# ESP.net
KiCad netlist of a schematic drawn in EAGLE
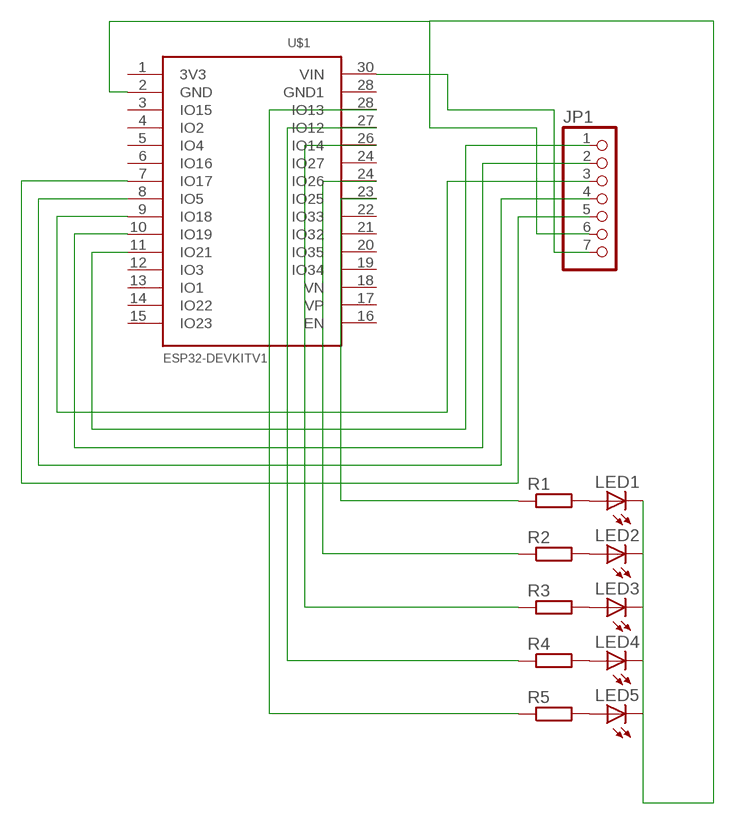
[diagram p0: schematic, sheet 1]

(export (version "E")
  (design (tool "Eeschema 10.0.6"))
  (components
    (comp (ref "JP1")
      (value "PINHD-1X7")
      (footprint "eagle-import:1X07")
      (libsource (lib "eagle-import") (part "PINHD-1X7"))
    )
    (comp (ref "LED1")
      (value "LED5MM")
      (footprint "eagle-import:LED5MM")
      (libsource (lib "eagle-import") (part "LED5MM"))
    )
    (comp (ref "LED2")
      (value "LED5MM")
      (footprint "eagle-import:LED5MM")
      (libsource (lib "eagle-import") (part "LED5MM"))
    )
    (comp (ref "LED3")
      (value "LED5MM")
      (footprint "eagle-import:LED5MM")
      (libsource (lib "eagle-import") (part "LED5MM"))
    )
    (comp (ref "LED4")
      (value "LED5MM")
      (footprint "eagle-import:LED5MM")
      (libsource (lib "eagle-import") (part "LED5MM"))
    )
    (comp (ref "LED5")
      (value "LED5MM")
      (footprint "eagle-import:LED5MM")
      (libsource (lib "eagle-import") (part "LED5MM"))
    )
    (comp (ref "R1")
      (value "R-EU_0207/7")
      (footprint "eagle-import:0207_7")
      (libsource (lib "eagle-import") (part "R-EU_0207/7"))
    )
    (comp (ref "R2")
      (value "R-EU_0207/7")
      (footprint "eagle-import:0207_7")
      (libsource (lib "eagle-import") (part "R-EU_0207/7"))
    )
    (comp (ref "R3")
      (value "R-EU_0207/7")
      (footprint "eagle-import:0207_7")
      (libsource (lib "eagle-import") (part "R-EU_0207/7"))
    )
    (comp (ref "R4")
      (value "R-EU_0207/7")
      (footprint "eagle-import:0207_7")
      (libsource (lib "eagle-import") (part "R-EU_0207/7"))
    )
    (comp (ref "R5")
      (value "R-EU_0207/7")
      (footprint "eagle-import:0207_7")
      (libsource (lib "eagle-import") (part "R-EU_0207/7"))
    )
    (comp (ref "U$1")
      (value "ESP32DEVKITV1")
      (footprint "eagle-import:ESP32-DEVKITV1")
      (libsource (lib "eagle-import") (part "ESP32DEVKITV1"))
    )
  )
  (nets
    (net (code "1") (name "Net-(LED1-C)") (class "Default")
      (node (ref "JP1") (pin "6") (pinfunction "6_6") (pintype "passive"))
      (node (ref "LED1") (pin "K") (pinfunction "C_K") (pintype "passive"))
      (node (ref "LED2") (pin "K") (pinfunction "C_K") (pintype "passive"))
      (node (ref "LED3") (pin "K") (pinfunction "C_K") (pintype "passive"))
      (node (ref "LED4") (pin "K") (pinfunction "C_K") (pintype "passive"))
      (node (ref "LED5") (pin "K") (pinfunction "C_K") (pintype "passive"))
      (node (ref "U$1") (pin "2") (pinfunction "GND_2") (pintype "bidirectional"))
    )
    (net (code "2") (name "Net-(LED1-PadA)") (class "Default")
      (node (ref "LED1") (pin "A") (pinfunction "A_A") (pintype "passive"))
      (node (ref "R1") (pin "2") (pinfunction "2_2") (pintype "passive"))
    )
    (net (code "3") (name "Net-(LED2-PadA)") (class "Default")
      (node (ref "LED2") (pin "A") (pinfunction "A_A") (pintype "passive"))
      (node (ref "R2") (pin "2") (pinfunction "2_2") (pintype "passive"))
    )
    (net (code "4") (name "Net-(LED3-PadA)") (class "Default")
      (node (ref "LED3") (pin "A") (pinfunction "A_A") (pintype "passive"))
      (node (ref "R3") (pin "2") (pinfunction "2_2") (pintype "passive"))
    )
    (net (code "5") (name "Net-(LED4-PadA)") (class "Default")
      (node (ref "LED4") (pin "A") (pinfunction "A_A") (pintype "passive"))
      (node (ref "R4") (pin "2") (pinfunction "2_2") (pintype "passive"))
    )
    (net (code "6") (name "Net-(LED5-PadA)") (class "Default")
      (node (ref "LED5") (pin "A") (pinfunction "A_A") (pintype "passive"))
      (node (ref "R5") (pin "2") (pinfunction "2_2") (pintype "passive"))
    )
    (net (code "7") (name "Net-(U$1-IO5)") (class "Default")
      (node (ref "JP1") (pin "4") (pinfunction "4_4") (pintype "passive"))
      (node (ref "U$1") (pin "8") (pinfunction "IO5_8") (pintype "bidirectional"))
    )
    (net (code "8") (name "Net-(U$1-IO12)") (class "Default")
      (node (ref "R4") (pin "1") (pinfunction "1_1") (pintype "passive"))
      (node (ref "U$1") (pin "27") (pinfunction "IO12_27") (pintype "bidirectional"))
    )
    (net (code "9") (name "Net-(U$1-IO13)") (class "Default")
      (node (ref "R5") (pin "1") (pinfunction "1_1") (pintype "passive"))
      (node (ref "U$1") (pin "28") (pinfunction "IO13_28") (pintype "bidirectional"))
    )
    (net (code "10") (name "Net-(U$1-IO14)") (class "Default")
      (node (ref "R3") (pin "1") (pinfunction "1_1") (pintype "passive"))
      (node (ref "U$1") (pin "26") (pinfunction "IO14_26") (pintype "bidirectional"))
    )
    (net (code "11") (name "Net-(U$1-IO17)") (class "Default")
      (node (ref "JP1") (pin "5") (pinfunction "5_5") (pintype "passive"))
      (node (ref "U$1") (pin "7") (pinfunction "IO17_7") (pintype "bidirectional"))
    )
    (net (code "12") (name "Net-(U$1-IO18)") (class "Default")
      (node (ref "JP1") (pin "3") (pinfunction "3_3") (pintype "passive"))
      (node (ref "U$1") (pin "9") (pinfunction "IO18_9") (pintype "bidirectional"))
    )
    (net (code "13") (name "Net-(U$1-IO19)") (class "Default")
      (node (ref "JP1") (pin "2") (pinfunction "2_2") (pintype "passive"))
      (node (ref "U$1") (pin "10") (pinfunction "IO19_10") (pintype "bidirectional"))
    )
    (net (code "14") (name "Net-(U$1-IO21)") (class "Default")
      (node (ref "JP1") (pin "1") (pinfunction "1_1") (pintype "passive"))
      (node (ref "U$1") (pin "11") (pinfunction "IO21_11") (pintype "bidirectional"))
    )
    (net (code "15") (name "Net-(U$1-IO25)") (class "Default")
      (node (ref "R1") (pin "1") (pinfunction "1_1") (pintype "passive"))
      (node (ref "U$1") (pin "23") (pinfunction "IO25_23") (pintype "bidirectional"))
    )
    (net (code "16") (name "Net-(U$1-IO26)") (class "Default")
      (node (ref "R2") (pin "1") (pinfunction "1_1") (pintype "passive"))
      (node (ref "U$1") (pin "24") (pinfunction "IO26_24") (pintype "bidirectional"))
    )
    (net (code "17") (name "Net-(U$1-VIN)") (class "Default")
      (node (ref "JP1") (pin "7") (pinfunction "7_7") (pintype "passive"))
      (node (ref "U$1") (pin "30") (pinfunction "VIN_30") (pintype "bidirectional"))
    )
    (net (code "18") (name "unconnected-(U$1-3V3-Pad1)") (class "Default")
      (node (ref "U$1") (pin "1") (pinfunction "3V3_1") (pintype "bidirectional"))
    )
    (net (code "19") (name "unconnected-(U$1-EN-Pad16)") (class "Default")
      (node (ref "U$1") (pin "16") (pinfunction "EN_16") (pintype "bidirectional"))
    )
    (net (code "20") (name "unconnected-(U$1-GND1-Pad28)") (class "Default")
      (node (ref "U$1") (pin "28") (pinfunction "GND1_28") (pintype "bidirectional"))
    )
    (net (code "21") (name "unconnected-(U$1-IO1-Pad13)") (class "Default")
      (node (ref "U$1") (pin "13") (pinfunction "IO1_13") (pintype "bidirectional"))
    )
    (net (code "22") (name "unconnected-(U$1-IO2-Pad4)") (class "Default")
      (node (ref "U$1") (pin "4") (pinfunction "IO2_4") (pintype "bidirectional"))
    )
    (net (code "23") (name "unconnected-(U$1-IO3-Pad12)") (class "Default")
      (node (ref "U$1") (pin "12") (pinfunction "IO3_12") (pintype "bidirectional"))
    )
    (net (code "24") (name "unconnected-(U$1-IO4-Pad5)") (class "Default")
      (node (ref "U$1") (pin "5") (pinfunction "IO4_5") (pintype "bidirectional"))
    )
    (net (code "25") (name "unconnected-(U$1-IO15-Pad3)") (class "Default")
      (node (ref "U$1") (pin "3") (pinfunction "IO15_3") (pintype "bidirectional"))
    )
    (net (code "26") (name "unconnected-(U$1-IO16-Pad6)") (class "Default")
      (node (ref "U$1") (pin "6") (pinfunction "IO16_6") (pintype "bidirectional"))
    )
    (net (code "27") (name "unconnected-(U$1-IO22-Pad14)") (class "Default")
      (node (ref "U$1") (pin "14") (pinfunction "IO22_14") (pintype "bidirectional"))
    )
    (net (code "28") (name "unconnected-(U$1-IO23-Pad15)") (class "Default")
      (node (ref "U$1") (pin "15") (pinfunction "IO23_15") (pintype "bidirectional"))
    )
    (net (code "29") (name "unconnected-(U$1-IO27-Pad24)") (class "Default")
      (node (ref "U$1") (pin "24") (pinfunction "IO27_24") (pintype "bidirectional"))
    )
    (net (code "30") (name "unconnected-(U$1-IO32-Pad21)") (class "Default")
      (node (ref "U$1") (pin "21") (pinfunction "IO32_21") (pintype "bidirectional"))
    )
    (net (code "31") (name "unconnected-(U$1-IO33-Pad22)") (class "Default")
      (node (ref "U$1") (pin "22") (pinfunction "IO33_22") (pintype "bidirectional"))
    )
    (net (code "32") (name "unconnected-(U$1-IO34-Pad19)") (class "Default")
      (node (ref "U$1") (pin "19") (pinfunction "IO34_19") (pintype "bidirectional"))
    )
    (net (code "33") (name "unconnected-(U$1-IO35-Pad20)") (class "Default")
      (node (ref "U$1") (pin "20") (pinfunction "IO35_20") (pintype "bidirectional"))
    )
    (net (code "34") (name "unconnected-(U$1-VN-Pad18)") (class "Default")
      (node (ref "U$1") (pin "18") (pinfunction "VN_18") (pintype "bidirectional"))
    )
    (net (code "35") (name "unconnected-(U$1-VP-Pad17)") (class "Default")
      (node (ref "U$1") (pin "17") (pinfunction "VP_17") (pintype "bidirectional"))
    )
  )
)
